# Power.net
KiCad netlist of a schematic drawn in Altium Designer
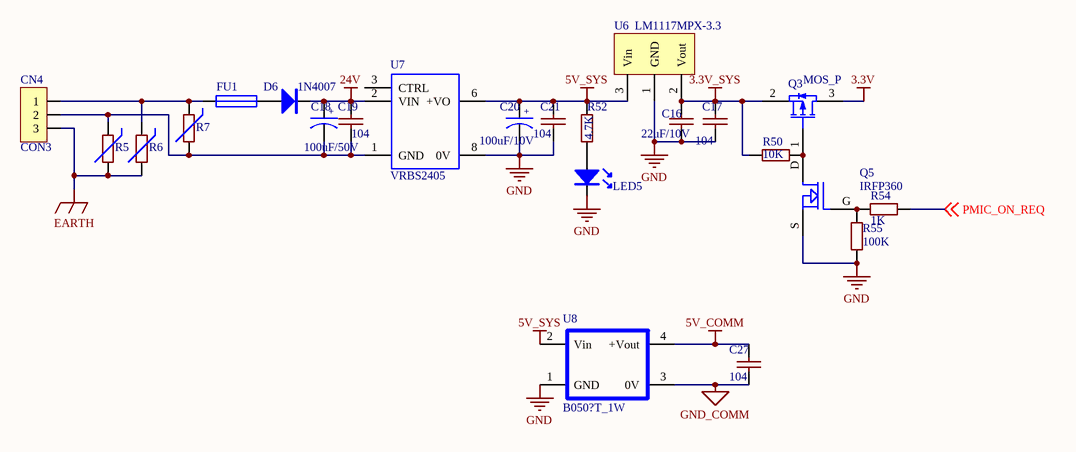
[diagram p0: Power.SchDoc]

(export (version "E")
  (design (tool "Eeschema 10.0.6"))
  (components
    (comp (ref "C16")
      (value "22uF/10V")
      (footprint "0805SMD_Cap")
      (description "贴片电容")
      (libsource (lib "ST_GND_Sch") (part "SMD_Cap"))
    )
    (comp (ref "C17")
      (value "104")
      (footprint "0805SMD_Cap")
      (description "贴片电容")
      (libsource (lib "ST_GND_Sch") (part "SMD_Cap"))
    )
    (comp (ref "C18")
      (value "100uF/50V")
      (footprint "电解电容-10")
      (description "电解电容")
      (libsource (lib "ST_GND_Sch") (part "CAP  POL"))
    )
    (comp (ref "C19")
      (value "104")
      (footprint "0805SMD_Cap")
      (description "贴片电容")
      (libsource (lib "ST_GND_Sch") (part "SMD_Cap"))
    )
    (comp (ref "C20")
      (value "100uF/10V")
      (footprint "电解电容-10")
      (description "电解电容")
      (libsource (lib "ST_GND_Sch") (part "CAP  POL"))
    )
    (comp (ref "C21")
      (value "104")
      (footprint "0805SMD_Cap")
      (description "贴片电容")
      (libsource (lib "ST_GND_Sch") (part "SMD_Cap"))
    )
    (comp (ref "C27")
      (value "104")
      (footprint "0805SMD_Cap")
      (description "贴片电容")
      (libsource (lib "ST_GND_Sch") (part "SMD_Cap"))
    )
    (comp (ref "CN4")
      (value "CON3")
      (footprint "WJ15EDGRM-3.81-3P-14-00A")
      (description "连接器")
      (libsource (lib "ST_GND_Sch") (part "CON3"))
    )
    (comp (ref "D6")
      (value "1N4007")
      (footprint "二极管SMA")
      (description "二极管")
      (libsource (lib "ST_GND_Sch") (part "DIODE"))
    )
    (comp (ref "FU1")
      (value "FUSE1")
      (footprint "RAD0.2")
      (description "保险")
      (libsource (lib "ST_GND_Sch") (part "FUSE1"))
    )
    (comp (ref "LED5")
      (value "LED")
      (footprint "发光二极管0805")
      (description "发光二极管")
      (libsource (lib "ST_GND_Sch") (part "LED"))
    )
    (comp (ref "Q3") (value "MOS_P") (footprint "SOT-23") (libsource (lib "ST_GND_Sch") (part "MOS_P")))
    (comp (ref "Q5")
      (value "IRFP360")
      (footprint "SOT-23 - MOS")
      (description "MOS管")
      (libsource (lib "ST_GND_Sch") (part "MOSFET N"))
    )
    (comp (ref "R5")
      (value "10d330K")
      (footprint "RAD0.2")
      (description "压敏电阻")
      (libsource (lib "ST_GND_Sch") (part "压敏电阻"))
    )
    (comp (ref "R6")
      (value "10d330K")
      (footprint "RAD0.2")
      (description "压敏电阻")
      (libsource (lib "ST_GND_Sch") (part "压敏电阻"))
    )
    (comp (ref "R7")
      (value "10d330K")
      (footprint "RAD0.2")
      (description "压敏电阻")
      (libsource (lib "ST_GND_Sch") (part "压敏电阻"))
    )
    (comp (ref "R50")
      (value "10K")
      (footprint "0805_SMD_R")
      (description "贴片电阻")
      (libsource (lib "") (part "SMD_0805_2"))
    )
    (comp (ref "R52")
      (value "4.7K")
      (footprint "0805_SMD_R")
      (description "贴片电阻")
      (libsource (lib "ST_GND_Sch") (part "SMD_0805"))
    )
    (comp (ref "R54")
      (value "1K")
      (footprint "0805_SMD_R")
      (description "贴片电阻")
      (libsource (lib "") (part "SMD_0805_2"))
    )
    (comp (ref "R55")
      (value "100K")
      (footprint "0805_SMD_R")
      (description "贴片电阻")
      (libsource (lib "") (part "SMD_0805_1"))
    )
    (comp (ref "U6")
      (value "LM1117MPX-3.3")
      (footprint "SOT-223")
      (description "LM1117 3.3V固定输出")
      (libsource (lib "ST_GND_Sch") (part "LM1117MPX-3.3"))
    )
    (comp (ref "U7") (value "VRBS2405") (footprint "VRB_S") (libsource (lib "ST_GND_Sch") (part "VRBS2405")))
    (comp (ref "U8")
      (value "B050?T_1W")
      (footprint "B0505S_1W")
      (libsource (lib "ST_GND_Sch") (part "B0505S_1W"))
    )
  )
  (nets
    (net (code "1") (name "3.3V") (class "Default")
      (node (ref "Q3") (pin "3") (pinfunction "D_3") (pintype "passive"))
    )
    (net (code "2") (name "3.3V_SYS") (class "Default")
      (node (ref "C16") (pin "1") (pintype "passive"))
      (node (ref "C17") (pin "1") (pintype "passive"))
      (node (ref "Q3") (pin "2") (pinfunction "S_2") (pintype "passive"))
      (node (ref "R50") (pin "2") (pinfunction "2_2") (pintype "passive"))
      (node (ref "U6") (pin "2") (pinfunction "Vout_2") (pintype "passive"))
    )
    (net (code "3") (name "5V_COMM") (class "Default")
      (node (ref "C27") (pin "1") (pintype "passive"))
      (node (ref "U8") (pin "4") (pinfunction "+Vout_4") (pintype "passive"))
    )
    (net (code "4") (name "5V_SYS") (class "Default")
      (node (ref "C20") (pin "1") (pinfunction "1_1") (pintype "passive"))
      (node (ref "C21") (pin "1") (pintype "passive"))
      (node (ref "R52") (pin "2") (pinfunction "2_2") (pintype "passive"))
      (node (ref "U6") (pin "3") (pinfunction "Vin_3") (pintype "passive"))
      (node (ref "U7") (pin "6") (pinfunction "+VO_6") (pintype "passive"))
      (node (ref "U8") (pin "2") (pinfunction "Vin_2") (pintype "passive"))
    )
    (net (code "5") (name "24V") (class "Default")
      (node (ref "C18") (pin "1") (pinfunction "1_1") (pintype "passive"))
      (node (ref "C19") (pin "1") (pintype "passive"))
      (node (ref "D6") (pin "K") (pintype "passive"))
      (node (ref "U7") (pin "2") (pinfunction "VIN_2") (pintype "passive"))
    )
    (net (code "6") (name "EARTH") (class "Default")
      (node (ref "CN4") (pin "3") (pinfunction "3_3") (pintype "passive"))
      (node (ref "R5") (pin "1") (pinfunction "1_1") (pintype "passive"))
      (node (ref "R6") (pin "1") (pinfunction "1_1") (pintype "passive"))
    )
    (net (code "7") (name "GND") (class "Default")
      (node (ref "C16") (pin "2") (pintype "passive"))
      (node (ref "C17") (pin "2") (pintype "passive"))
      (node (ref "C20") (pin "2") (pinfunction "2_2") (pintype "passive"))
      (node (ref "C21") (pin "2") (pintype "passive"))
      (node (ref "LED5") (pin "K") (pintype "passive"))
      (node (ref "Q5") (pin "S") (pinfunction "SOURCE_S") (pintype "passive"))
      (node (ref "R55") (pin "2") (pinfunction "2_2") (pintype "passive"))
      (node (ref "U6") (pin "1") (pinfunction "GND_1") (pintype "passive"))
      (node (ref "U7") (pin "8") (pinfunction "0V_8") (pintype "passive"))
      (node (ref "U8") (pin "1") (pinfunction "GND_1") (pintype "passive"))
    )
    (net (code "8") (name "GND_COMM") (class "Default")
      (node (ref "C27") (pin "2") (pintype "passive"))
      (node (ref "U8") (pin "3") (pinfunction "0V_3") (pintype "passive"))
    )
    (net (code "9") (name "Net-(CN4-Pad1)") (class "Default")
      (node (ref "CN4") (pin "1") (pinfunction "1_1") (pintype "passive"))
      (node (ref "FU1") (pin "1") (pintype "passive"))
      (node (ref "R6") (pin "2") (pinfunction "2_2") (pintype "passive"))
      (node (ref "R7") (pin "2") (pinfunction "2_2") (pintype "passive"))
    )
    (net (code "10") (name "Net-(D6-PadA)") (class "Default")
      (node (ref "D6") (pin "A") (pintype "passive"))
      (node (ref "FU1") (pin "2") (pintype "passive"))
    )
    (net (code "11") (name "Net-(LED5-PadA)") (class "Default")
      (node (ref "LED5") (pin "A") (pintype "passive"))
      (node (ref "R52") (pin "1") (pinfunction "1_1") (pintype "passive"))
    )
    (net (code "12") (name "Net-(Q3-G)") (class "Default")
      (node (ref "Q3") (pin "1") (pinfunction "G_1") (pintype "passive"))
      (node (ref "Q5") (pin "D") (pinfunction "DRAIN_D") (pintype "passive"))
      (node (ref "R50") (pin "1") (pinfunction "1_1") (pintype "passive"))
    )
    (net (code "13") (name "Net-(Q5-GATE)") (class "Default")
      (node (ref "Q5") (pin "G") (pinfunction "GATE_G") (pintype "passive"))
      (node (ref "R54") (pin "2") (pinfunction "2_2") (pintype "passive"))
      (node (ref "R55") (pin "1") (pinfunction "1_1") (pintype "passive"))
    )
    (net (code "14") (name "Net-(U7-GND)") (class "Default")
      (node (ref "C18") (pin "2") (pinfunction "2_2") (pintype "passive"))
      (node (ref "C19") (pin "2") (pintype "passive"))
      (node (ref "CN4") (pin "2") (pinfunction "2_2") (pintype "passive"))
      (node (ref "R5") (pin "2") (pinfunction "2_2") (pintype "passive"))
      (node (ref "R7") (pin "1") (pinfunction "1_1") (pintype "passive"))
      (node (ref "U7") (pin "1") (pinfunction "GND_1") (pintype "passive"))
    )
    (net (code "15") (name "PMIC_ON_REQ") (class "Default")
      (node (ref "R54") (pin "1") (pinfunction "1_1") (pintype "passive"))
    )
    (net (code "16") (name "unconnected-(U7-CTRL-Pad3)") (class "Default")
      (node (ref "U7") (pin "3") (pinfunction "CTRL_3") (pintype "passive"))
    )
    (net (code "17") (name "unconnected-(U7-NC-Pad5)") (class "Default")
      (node (ref "U7") (pin "5") (pinfunction "NC_5") (pintype "passive"))
    )
    (net (code "18") (name "unconnected-(U7-NC-Pad7)") (class "Default")
      (node (ref "U7") (pin "7") (pinfunction "NC_7") (pintype "passive"))
    )
  )
)
